# Watchdog.net
KiCad netlist of a schematic drawn in Altium Designer
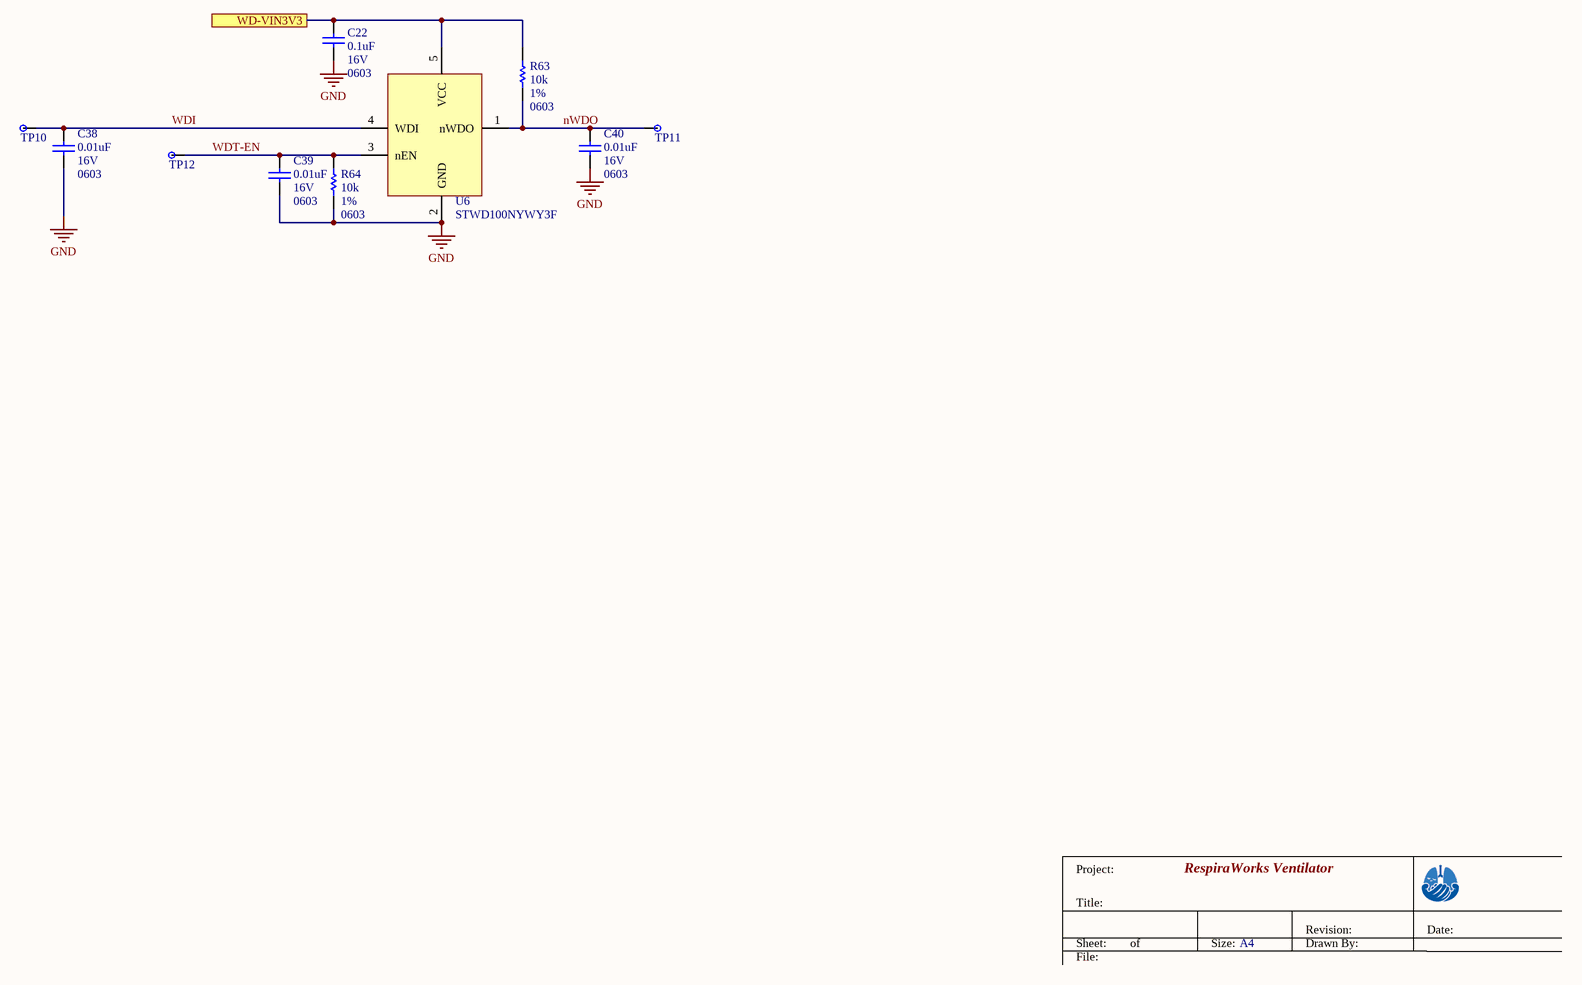
[diagram p0: Watchdog.SchDoc]

(export (version "E")
  (design (tool "Eeschema 10.0.6"))
  (components
    (comp (ref "C22")
      (value "0.1uF")
      (footprint "CAP0603")
      (description "Cap 0603")
      (fields
        (field (name "MANUFACTURER") "Yageo")
        (field (name "VOLTAGE") "16V")
        (field (name "PCB PACKAGE") "0603")
        (field (name "Comment") "CAP 0603")
      )
      (libsource (lib "generic") (part "CAP 0603"))
    )
    (comp (ref "C38")
      (value "0.01uF")
      (footprint "CAP0603")
      (description "Cap 0603")
      (fields
        (field (name "MANUFACTURER") "Samsung")
        (field (name "VOLTAGE") "16V")
        (field (name "PCB PACKAGE") "0603")
        (field (name "Comment") "CAP 0603")
      )
      (libsource (lib "generic") (part "CAP 0603"))
    )
    (comp (ref "C39")
      (value "0.01uF")
      (footprint "CAP0603")
      (description "Cap 0603")
      (fields
        (field (name "MANUFACTURER") "Samsung")
        (field (name "VOLTAGE") "16V")
        (field (name "PCB PACKAGE") "0603")
        (field (name "Comment") "CAP 0603")
      )
      (libsource (lib "generic") (part "CAP 0603"))
    )
    (comp (ref "C40")
      (value "0.01uF")
      (footprint "CAP0603")
      (description "Cap 0603")
      (fields
        (field (name "MANUFACTURER") "Samsung")
        (field (name "VOLTAGE") "16V")
        (field (name "PCB PACKAGE") "0603")
        (field (name "Comment") "CAP 0603")
      )
      (libsource (lib "generic") (part "CAP 0603"))
    )
    (comp (ref "R63")
      (value "10k")
      (footprint "RES0603")
      (description "Res 0603")
      (fields
        (field (name "MANUFACTURER") "Panasonic")
        (field (name "PCB PACKAGE") "0603")
        (field (name "TOLERANCE") "1%")
        (field (name "Comment") "RES 0603")
      )
      (libsource (lib "generic") (part "RES 0603"))
    )
    (comp (ref "R64")
      (value "10k")
      (footprint "RES0603")
      (description "Res 0603")
      (fields
        (field (name "MANUFACTURER") "Panasonic")
        (field (name "PCB PACKAGE") "0603")
        (field (name "TOLERANCE") "1%")
        (field (name "Comment") "RES 0603")
      )
      (libsource (lib "generic") (part "RES 0603"))
    )
    (comp (ref "TP10")
      (value "TP-SMT")
      (footprint "TP-5015")
      (description "Keystone 5015 SMT Mini Testpoint")
      (fields (field (name "MANUFACTURER") "Keystone") (field (name "TOLERANCE") "5015"))
      (libsource (lib "generic") (part "TP-SMT"))
    )
    (comp (ref "TP11")
      (value "TP-SMT")
      (footprint "TP-5015")
      (description "Keystone 5015 SMT Mini Testpoint")
      (fields (field (name "MANUFACTURER") "Keystone") (field (name "TOLERANCE") "5015"))
      (libsource (lib "generic") (part "TP-SMT"))
    )
    (comp (ref "TP12")
      (value "TP-SMT")
      (footprint "TP-5015")
      (description "Keystone 5015 SMT Mini Testpoint")
      (fields (field (name "MANUFACTURER") "Keystone") (field (name "TOLERANCE") "5015"))
      (libsource (lib "generic") (part "TP-SMT"))
    )
    (comp (ref "U6")
      (value "STWD100NYWY3F")
      (footprint "5-SOT23")
      (description "Watchdog Timer Circuit, 1.6s timeout")
      (fields (field (name "MANUFACTURER") "ST"))
      (libsource (lib "st") (part "STWD100NYWY3F"))
    )
  )
  (nets
    (net (code "1") (name "/WD-VIN3V3") (class "Default")
      (node (ref "C22") (pin "1") (pinfunction "1_1") (pintype "passive"))
      (node (ref "R63") (pin "2") (pinfunction "2_2") (pintype "passive"))
      (node (ref "U6") (pin "5") (pinfunction "VCC_5") (pintype "passive"))
    )
    (net (code "2") (name "/WDI") (class "Default")
      (node (ref "C38") (pin "1") (pinfunction "1_1") (pintype "passive"))
      (node (ref "TP10") (pin "1") (pinfunction "1_1") (pintype "passive"))
      (node (ref "U6") (pin "4") (pinfunction "WDI_4") (pintype "passive"))
    )
    (net (code "3") (name "/WDT-EN") (class "Default")
      (node (ref "C39") (pin "1") (pinfunction "1_1") (pintype "passive"))
      (node (ref "R64") (pin "2") (pinfunction "2_2") (pintype "passive"))
      (node (ref "TP12") (pin "1") (pinfunction "1_1") (pintype "passive"))
      (node (ref "U6") (pin "3") (pinfunction "nEN_3") (pintype "passive"))
    )
    (net (code "4") (name "/nWDO") (class "Default")
      (node (ref "C40") (pin "1") (pinfunction "1_1") (pintype "passive"))
      (node (ref "R63") (pin "1") (pinfunction "1_1") (pintype "passive"))
      (node (ref "TP11") (pin "1") (pinfunction "1_1") (pintype "passive"))
      (node (ref "U6") (pin "1") (pinfunction "nWDO_1") (pintype "passive"))
    )
    (net (code "5") (name "GND") (class "Default")
      (node (ref "C22") (pin "2") (pinfunction "2_2") (pintype "passive"))
      (node (ref "C38") (pin "2") (pinfunction "2_2") (pintype "passive"))
      (node (ref "C39") (pin "2") (pinfunction "2_2") (pintype "passive"))
      (node (ref "C40") (pin "2") (pinfunction "2_2") (pintype "passive"))
      (node (ref "R64") (pin "1") (pinfunction "1_1") (pintype "passive"))
      (node (ref "U6") (pin "2") (pinfunction "GND_2") (pintype "passive"))
    )
  )
)
